# TOP.net
KiCad netlist of a schematic drawn in Altium Designer
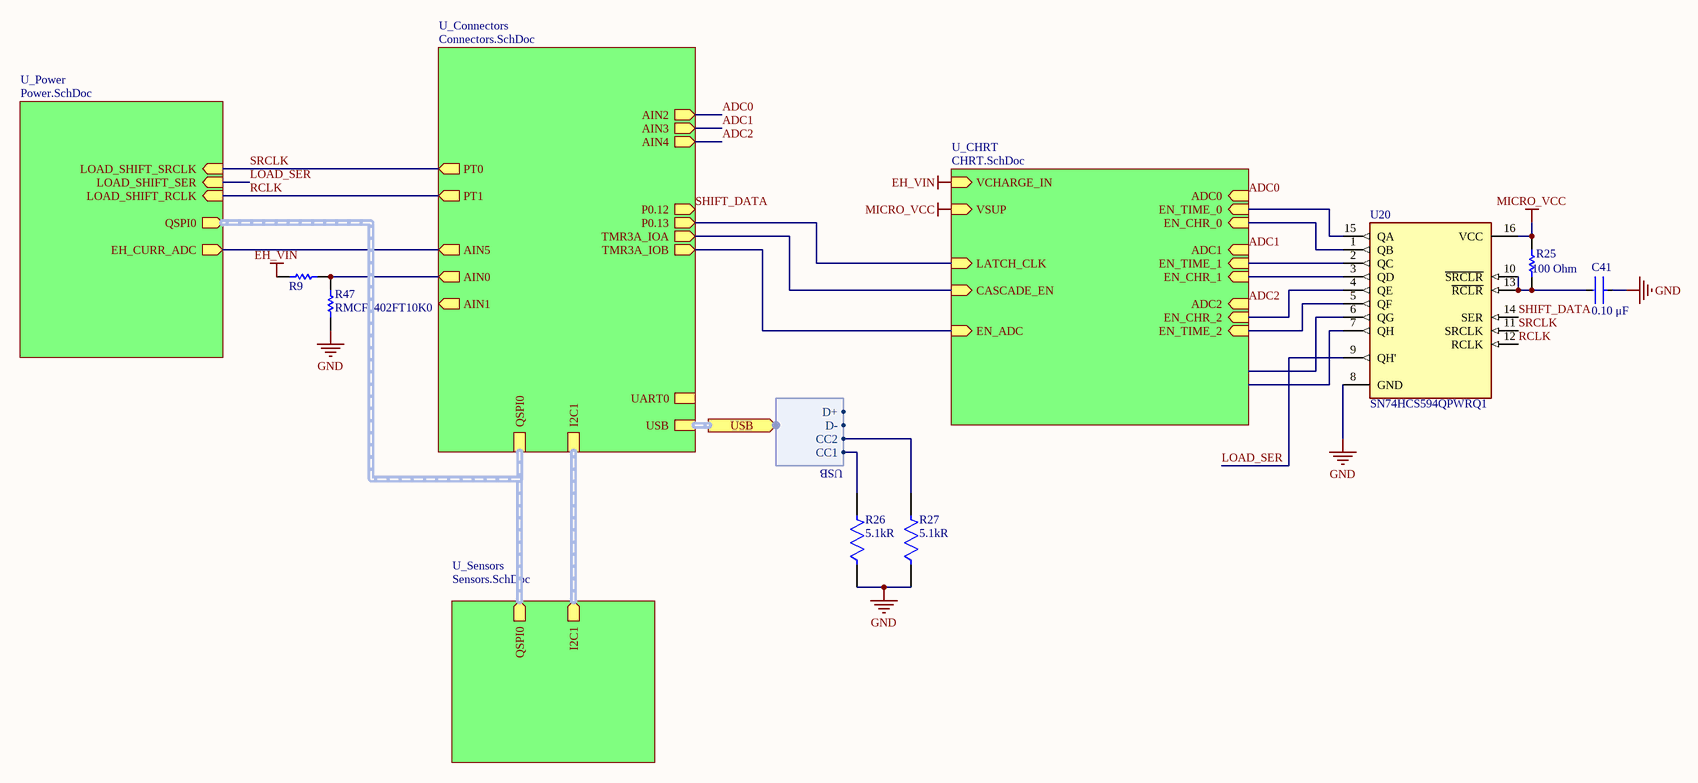
[diagram p0: TOP.SchDoc]

(export (version "E")
  (design (tool "Eeschema 10.0.6"))
  (components
    (comp (ref "C41")
      (value "C0402C104K8PACTU")
      (footprint "FP-C0402-BB-MFG")
      (description "CAP CER 0.1UF 10V X5R 0402")
      (fields
        (field (name "CAPACITANCE") "0.10 μF")
        (field (name "MANUFACTURER") "Kemet")
        (field (name "TOLERANCE") "0.1")
      )
      (libsource (lib "Altium Content Vault") (part "b4654b650e69147ec39a6b967a45e02"))
    )
    (comp (ref "R9")
      (value "RC0402JR-075M6L")
      (footprint "RESC1005X40X25ML05T10")
      (fields (field (name "MANUFACTURER") "Yageo / Phycomp"))
      (libsource (lib "Altium Content Vault") (part "RES"))
    )
    (comp (ref "R25")
      (value "ERJ-2RKF1000X")
      (footprint "RESC1005X40X25LL05T05")
      (description "Chip Resistor, 100 Ohm, +/- 1%, 100 mW, -55 to 155 degC, 0402 (1005 Metric), RoHS, Tape and Reel")
      (fields
        (field (name "MANUFACTURER") "Basic Passives")
        (field (name "TOLERANCE") "1%")
        (field (name "RESISTANCE") "100 Ohm")
      )
      (libsource (lib "Altium Content Vault") (part "RES-2"))
    )
    (comp (ref "R26")
      (value "CRCW04025K10FKED")
      (footprint "FP-CRCW0402-e3-IPC_A")
      (description "RES Thick Film, 5.1kΩ, 1%, 0.063W, 100ppm/°C, 0402")
      (fields (field (name "TOLERANCE") "1%") (field (name "RESISTANCE") "5.1kR"))
      (libsource (lib "Altium Content Vault") (part "1029c3af85768c4190bb7ad29bc67b5"))
    )
    (comp (ref "R27")
      (value "CRCW04025K10FKED")
      (footprint "FP-CRCW0402-e3-IPC_A")
      (description "RES Thick Film, 5.1kΩ, 1%, 0.063W, 100ppm/°C, 0402")
      (fields (field (name "TOLERANCE") "1%") (field (name "RESISTANCE") "5.1kR"))
      (libsource (lib "Altium Content Vault") (part "1029c3af85768c4190bb7ad29bc67b5"))
    )
    (comp (ref "R47")
      (value "RMCF0402FT10K0")
      (footprint "RESC1005X40X25ML05T10")
      (fields (field (name "MANUFACTURER") "Yageo / Phycomp") (field (name "PART NUMBER") "RC0402FR-071ML"))
      (libsource (lib "Altium Content Vault") (part "RES"))
    )
    (comp (ref "U20")
      (value "SN74HCS594QPWRQ1")
      (footprint "FP-PW0016A-IPC_A")
      (description "AUTOMOTIVE 8-BIT SHIFT REGISTERS")
      (libsource (lib "Altium Content Vault") (part "ee4c9120f52ff91501c7aa2bff67eb2"))
    )
  )
  (nets
    (net (code "5") (name "/AIN0") (class "Default")
      (node (ref "R47") (pin "2") (pinfunction "2_2") (pintype "passive"))
      (node (ref "R9") (pin "2") (pinfunction "2_2") (pintype "passive"))
    )
    (net (code "8") (name "/CC1") (class "Default")
      (node (ref "R26") (pin "2") (pinfunction "2_2") (pintype "passive"))
    )
    (net (code "9") (name "/CC2") (class "Default")
      (node (ref "R27") (pin "2") (pinfunction "2_2") (pintype "passive"))
    )
    (net (code "10") (name "/EN_CHR_0") (class "Default")
      (node (ref "U20") (pin "1") (pinfunction "QB_1") (pintype "output"))
    )
    (net (code "11") (name "/EN_CHR_1") (class "Default")
      (node (ref "U20") (pin "3") (pinfunction "QD_3") (pintype "output"))
    )
    (net (code "12") (name "/EN_CHR_2") (class "Default")
      (node (ref "U20") (pin "4") (pinfunction "QE_4") (pintype "output"))
    )
    (net (code "13") (name "/EN_TIME_0") (class "Default")
      (node (ref "U20") (pin "15") (pinfunction "QA_15") (pintype "output"))
    )
    (net (code "14") (name "/EN_TIME_1") (class "Default")
      (node (ref "U20") (pin "2") (pinfunction "QC_2") (pintype "output"))
    )
    (net (code "15") (name "/EN_TIME_2") (class "Default")
      (node (ref "U20") (pin "5") (pinfunction "QF_5") (pintype "output"))
    )
    (net (code "17") (name "/LOAD_SER") (class "Default")
      (node (ref "U20") (pin "9") (pinfunction "QH'_9") (pintype "output"))
    )
    (net (code "20") (name "/RCLK") (class "Default")
      (node (ref "U20") (pin "12") (pinfunction "RCLK_12") (pintype "input"))
    )
    (net (code "21") (name "/SHIFT_DATA") (class "Default")
      (node (ref "U20") (pin "14") (pinfunction "SER_14") (pintype "input"))
    )
    (net (code "22") (name "/SRCLK") (class "Default")
      (node (ref "U20") (pin "11") (pinfunction "SRCLK_11") (pintype "input"))
    )
    (net (code "27") (name "EH_VIN") (class "Default")
      (node (ref "R9") (pin "1") (pinfunction "1_1") (pintype "passive"))
    )
    (net (code "28") (name "GND") (class "Default")
      (node (ref "C41") (pin "1") (pinfunction "1_1") (pintype "passive"))
      (node (ref "R26") (pin "1") (pinfunction "1_1") (pintype "passive"))
      (node (ref "R27") (pin "1") (pinfunction "1_1") (pintype "passive"))
      (node (ref "R47") (pin "1") (pinfunction "1_1") (pintype "passive"))
      (node (ref "U20") (pin "8") (pinfunction "GND_8") (pintype "power_in"))
    )
    (net (code "29") (name "MICRO_VCC") (class "Default")
      (node (ref "R25") (pin "2") (pinfunction "2_2") (pintype "passive"))
      (node (ref "U20") (pin "16") (pinfunction "VCC_16") (pintype "power_in"))
    )
    (net (code "30") (name "Net-(U20-~{RCLR})") (class "Default")
      (node (ref "C41") (pin "2") (pinfunction "2_2") (pintype "passive"))
      (node (ref "R25") (pin "1") (pinfunction "1_1") (pintype "passive"))
      (node (ref "U20") (pin "10") (pinfunction "~{SRCLR}_10") (pintype "input"))
      (node (ref "U20") (pin "13") (pinfunction "~{RCLR}_13") (pintype "input"))
    )
    (net (code "31") (name "unconnected-(U20-QG-Pad6)") (class "Default")
      (node (ref "U20") (pin "6") (pinfunction "QG_6") (pintype "output"))
    )
    (net (code "32") (name "unconnected-(U20-QH-Pad7)") (class "Default")
      (node (ref "U20") (pin "7") (pinfunction "QH_7") (pintype "output"))
    )
  )
)
